# Alimentacion.net
KiCad netlist of a schematic drawn in Altium Designer
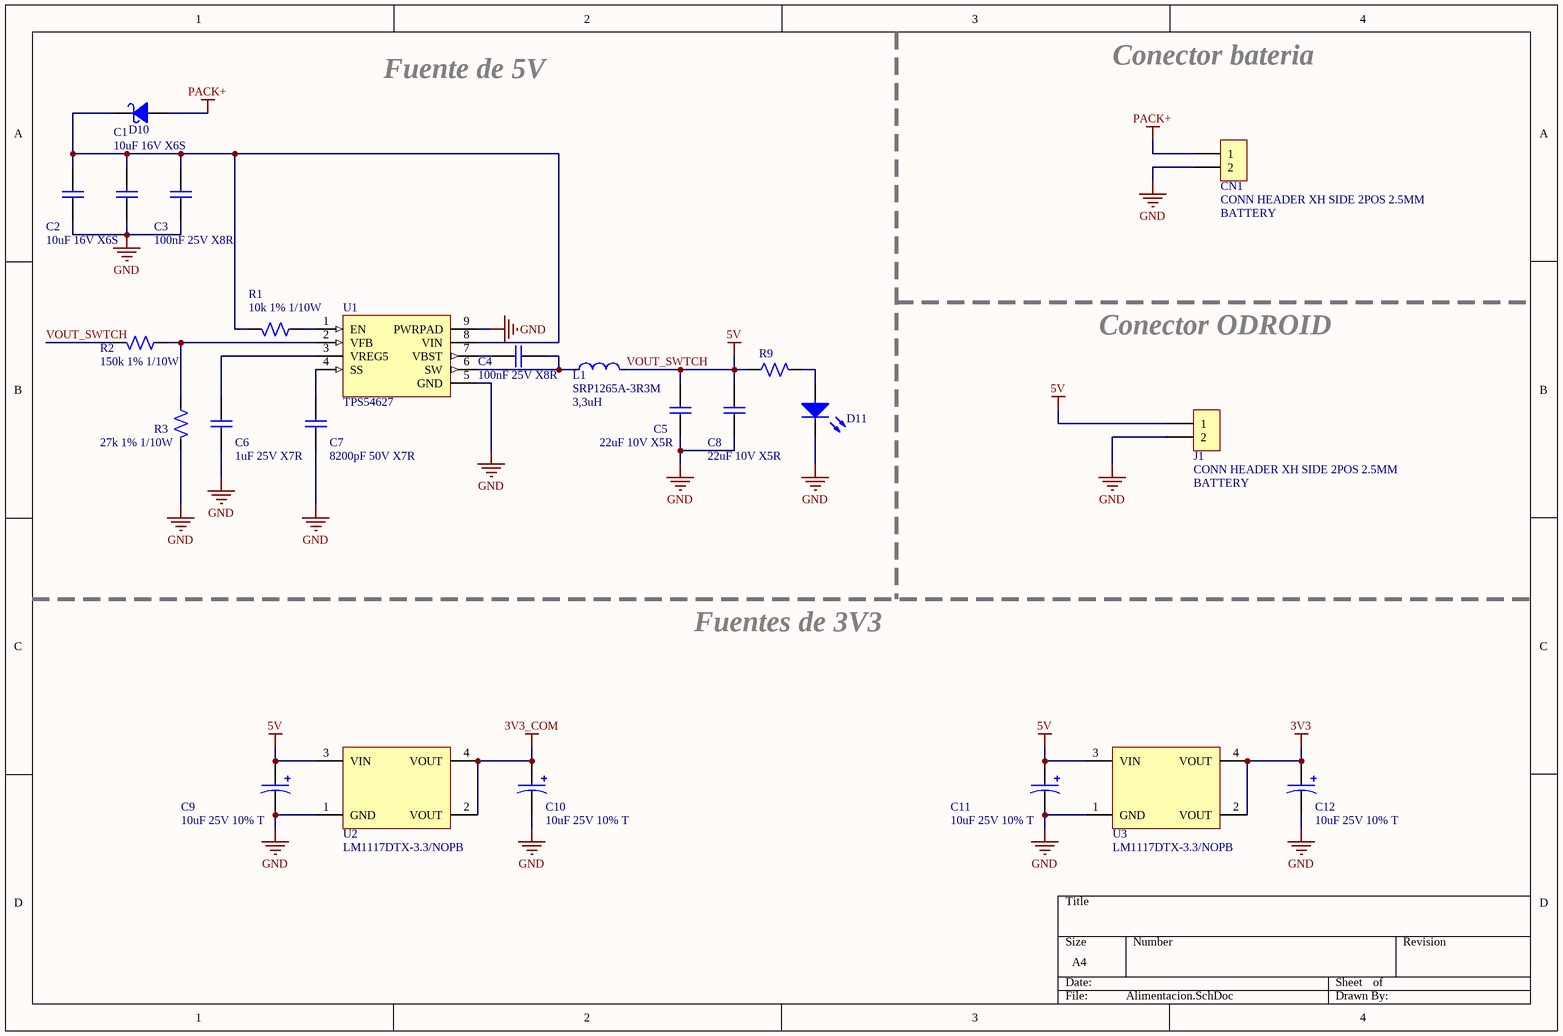
[diagram p0: Alimentacion.SchDoc]

(export (version "E")
  (design (tool "Eeschema 10.0.6"))
  (components
    (comp (ref "C1")
      (value "10uF 16V X6S")
      (footprint "C1206")
      (description "Capacitor de placas paralelas")
      (libsource (lib "HW_Dron_V2") (part "Capacitor"))
    )
    (comp (ref "C2")
      (value "10uF 16V X6S")
      (footprint "C1206")
      (description "Capacitor de placas paralelas")
      (libsource (lib "HW_Dron_V2") (part "Capacitor"))
    )
    (comp (ref "C3")
      (value "100nF 25V X8R")
      (footprint "C1206")
      (description "Capacitor de placas paralelas")
      (libsource (lib "HW_Dron_V2") (part "Capacitor"))
    )
    (comp (ref "C4")
      (value "100nF 25V X8R")
      (footprint "C0603")
      (description "Capacitor de placas paralelas")
      (libsource (lib "HW_Dron_V2") (part "Capacitor"))
    )
    (comp (ref "C5")
      (value "22uF 10V X5R")
      (footprint "C1206")
      (description "Capacitor de placas paralelas")
      (libsource (lib "HW_Dron_V2") (part "Capacitor"))
    )
    (comp (ref "C6")
      (value "1uF 25V X7R")
      (footprint "C0603")
      (description "Capacitor de placas paralelas")
      (libsource (lib "HW_Dron_V2") (part "Capacitor"))
    )
    (comp (ref "C7")
      (value "8200pF 50V X7R")
      (footprint "C0603")
      (description "Capacitor de placas paralelas")
      (libsource (lib "HW_Dron_V2") (part "Capacitor"))
    )
    (comp (ref "C8")
      (value "22uF 10V X5R")
      (footprint "C1206")
      (description "Capacitor de placas paralelas")
      (libsource (lib "HW_Dron_V2") (part "Capacitor"))
    )
    (comp (ref "C9")
      (value "10uF 25V 10% T")
      (footprint "AVX_C")
      (description "Capacitor polarizado")
      (libsource (lib "HW_Dron_V2") (part "CapaPol"))
    )
    (comp (ref "C10")
      (value "10uF 25V 10% T")
      (footprint "AVX_C")
      (description "Capacitor polarizado")
      (libsource (lib "HW_Dron_V2") (part "CapaPol"))
    )
    (comp (ref "C11")
      (value "10uF 25V 10% T")
      (footprint "AVX_C")
      (description "Capacitor polarizado")
      (libsource (lib "HW_Dron_V2") (part "CapaPol"))
    )
    (comp (ref "C12")
      (value "10uF 25V 10% T")
      (footprint "AVX_C")
      (description "Capacitor polarizado")
      (libsource (lib "HW_Dron_V2") (part "CapaPol"))
    )
    (comp (ref "CN1")
      (value "CONN HEADER XH SIDE 2POS 2.5MM")
      (footprint "S2B-XH-A")
      (description "Header, 2-pin")
      (fields (field (name "ALTIUM_UNNAMED_1") "BATTERY"))
      (libsource (lib "HW_Dron_V2") (part "Header_2"))
    )
    (comp (ref "D10")
      (value "Schottky")
      (footprint "SMC (DO-214AB)")
      (description "Diodo Schottky")
      (libsource (lib "HW_Dron_V2") (part "Schottky"))
    )
    (comp (ref "D11")
      (value "Led")
      (footprint "LED_0805")
      (description "Diodo Led")
      (libsource (lib "HW_Dron_V2") (part "Led"))
    )
    (comp (ref "J1")
      (value "CONN HEADER XH SIDE 2POS 2.5MM")
      (footprint "5V_OUT")
      (description "Header, 2-pin")
      (fields (field (name "ALTIUM_UNNAMED_1") "BATTERY"))
      (libsource (lib "HW_Dron_V2") (part "Header_2"))
    )
    (comp (ref "L1")
      (value "SRP1265A-3R3M")
      (footprint "SRP1265A")
      (description "Inductor")
      (fields (field (name "VALOR") "3,3uH"))
      (libsource (lib "HW_Dron_V2") (part "Inductor"))
    )
    (comp (ref "R1")
      (value "10k 1% 1/10W")
      (footprint "R0603")
      (description "Resistencia")
      (libsource (lib "HW_Dron_V2") (part "Resistor"))
    )
    (comp (ref "R2")
      (value "150k 1% 1/10W")
      (footprint "R0603")
      (description "Resistencia")
      (libsource (lib "HW_Dron_V2") (part "Resistor"))
    )
    (comp (ref "R3")
      (value "27k 1% 1/10W")
      (footprint "R0603")
      (description "Resistencia")
      (libsource (lib "HW_Dron_V2") (part "Resistor"))
    )
    (comp (ref "R9")
      (value "~")
      (footprint "R0603")
      (description "Resistencia")
      (libsource (lib "HW_Dron_V2") (part "Resistor"))
    )
    (comp (ref "U1")
      (value "TPS54627")
      (footprint "HSOP-8")
      (description "4.5-V to 18-V Input, 6-A Synchronous Step-Down Converter")
      (libsource (lib "HW_Dron_V2") (part "TPS54627"))
    )
    (comp (ref "U2")
      (value "LM1117DTX-3.3/NOPB")
      (footprint "DPAK")
      (description "Low dropout oscilator")
      (libsource (lib "HW_Dron_V2") (part "LM1117"))
    )
    (comp (ref "U3")
      (value "LM1117DTX-3.3/NOPB")
      (footprint "DPAK")
      (description "Low dropout oscilator")
      (libsource (lib "HW_Dron_V2") (part "LM1117"))
    )
  )
  (nets
    (net (code "1") (name "3V3") (class "Default")
      (node (ref "C12") (pin "1") (pinfunction "1_1") (pintype "passive"))
      (node (ref "U3") (pin "2") (pinfunction "VOUT_2") (pintype "power_in"))
      (node (ref "U3") (pin "4") (pinfunction "VOUT_4") (pintype "power_in"))
    )
    (net (code "2") (name "3V3_COM") (class "Default")
      (node (ref "C10") (pin "1") (pinfunction "1_1") (pintype "passive"))
      (node (ref "U2") (pin "2") (pinfunction "VOUT_2") (pintype "power_in"))
      (node (ref "U2") (pin "4") (pinfunction "VOUT_4") (pintype "power_in"))
    )
    (net (code "3") (name "5V") (class "Default")
      (node (ref "C11") (pin "1") (pinfunction "1_1") (pintype "passive"))
      (node (ref "C5") (pin "1") (pinfunction "1_1") (pintype "passive"))
      (node (ref "C8") (pin "1") (pinfunction "1_1") (pintype "passive"))
      (node (ref "C9") (pin "1") (pinfunction "1_1") (pintype "passive"))
      (node (ref "J1") (pin "1") (pinfunction "1_1") (pintype "passive"))
      (node (ref "L1") (pin "2") (pinfunction "2_2") (pintype "passive"))
      (node (ref "R2") (pin "2") (pinfunction "2_2") (pintype "passive"))
      (node (ref "R9") (pin "1") (pinfunction "1_1") (pintype "passive"))
      (node (ref "U2") (pin "3") (pinfunction "VIN_3") (pintype "power_in"))
      (node (ref "U3") (pin "3") (pinfunction "VIN_3") (pintype "power_in"))
    )
    (net (code "4") (name "GND") (class "Default")
      (node (ref "C1") (pin "2") (pinfunction "2_2") (pintype "passive"))
      (node (ref "C10") (pin "2") (pinfunction "2_2") (pintype "passive"))
      (node (ref "C11") (pin "2") (pinfunction "2_2") (pintype "passive"))
      (node (ref "C12") (pin "2") (pinfunction "2_2") (pintype "passive"))
      (node (ref "C2") (pin "2") (pinfunction "2_2") (pintype "passive"))
      (node (ref "C3") (pin "2") (pinfunction "2_2") (pintype "passive"))
      (node (ref "C5") (pin "2") (pinfunction "2_2") (pintype "passive"))
      (node (ref "C6") (pin "2") (pinfunction "2_2") (pintype "passive"))
      (node (ref "C7") (pin "2") (pinfunction "2_2") (pintype "passive"))
      (node (ref "C8") (pin "2") (pinfunction "2_2") (pintype "passive"))
      (node (ref "C9") (pin "2") (pinfunction "2_2") (pintype "passive"))
      (node (ref "CN1") (pin "2") (pinfunction "2_2") (pintype "passive"))
      (node (ref "D11") (pin "2") (pinfunction "2_2") (pintype "passive"))
      (node (ref "J1") (pin "2") (pinfunction "2_2") (pintype "passive"))
      (node (ref "R3") (pin "2") (pinfunction "2_2") (pintype "passive"))
      (node (ref "U1") (pin "5") (pinfunction "GND_5") (pintype "power_in"))
      (node (ref "U1") (pin "9") (pinfunction "PWRPAD_9") (pintype "power_in"))
      (node (ref "U2") (pin "1") (pinfunction "GND_1") (pintype "power_in"))
      (node (ref "U3") (pin "1") (pinfunction "GND_1") (pintype "power_in"))
    )
    (net (code "5") (name "Net-(D11-Pad1)") (class "Default")
      (node (ref "D11") (pin "1") (pinfunction "1_1") (pintype "passive"))
      (node (ref "R9") (pin "2") (pinfunction "2_2") (pintype "passive"))
    )
    (net (code "6") (name "Net-(U1-EN)") (class "Default")
      (node (ref "R1") (pin "1") (pinfunction "1_1") (pintype "passive"))
      (node (ref "U1") (pin "1") (pinfunction "EN_1") (pintype "input"))
    )
    (net (code "7") (name "Net-(U1-SS)") (class "Default")
      (node (ref "C7") (pin "1") (pinfunction "1_1") (pintype "passive"))
      (node (ref "U1") (pin "4") (pinfunction "SS_4") (pintype "input"))
    )
    (net (code "8") (name "Net-(U1-SW)") (class "Default")
      (node (ref "C4") (pin "2") (pinfunction "2_2") (pintype "passive"))
      (node (ref "L1") (pin "1") (pinfunction "1_1") (pintype "passive"))
      (node (ref "U1") (pin "6") (pinfunction "SW_6") (pintype "output"))
    )
    (net (code "9") (name "Net-(U1-VBST)") (class "Default")
      (node (ref "C4") (pin "1") (pinfunction "1_1") (pintype "passive"))
      (node (ref "U1") (pin "7") (pinfunction "VBST_7") (pintype "output"))
    )
    (net (code "10") (name "Net-(U1-VFB)") (class "Default")
      (node (ref "R2") (pin "1") (pinfunction "1_1") (pintype "passive"))
      (node (ref "R3") (pin "1") (pinfunction "1_1") (pintype "passive"))
      (node (ref "U1") (pin "2") (pinfunction "VFB_2") (pintype "input"))
    )
    (net (code "11") (name "Net-(U1-VIN)") (class "Default")
      (node (ref "C1") (pin "1") (pinfunction "1_1") (pintype "passive"))
      (node (ref "C2") (pin "1") (pinfunction "1_1") (pintype "passive"))
      (node (ref "C3") (pin "1") (pinfunction "1_1") (pintype "passive"))
      (node (ref "D10") (pin "2") (pinfunction "2_2") (pintype "passive"))
      (node (ref "R1") (pin "2") (pinfunction "2_2") (pintype "passive"))
      (node (ref "U1") (pin "8") (pinfunction "VIN_8") (pintype "power_in"))
    )
    (net (code "12") (name "Net-(U1-VREG5)") (class "Default")
      (node (ref "C6") (pin "1") (pinfunction "1_1") (pintype "passive"))
      (node (ref "U1") (pin "3") (pinfunction "VREG5_3") (pintype "passive"))
    )
    (net (code "13") (name "PACK+") (class "Default")
      (node (ref "CN1") (pin "1") (pinfunction "1_1") (pintype "passive"))
      (node (ref "D10") (pin "1") (pinfunction "1_1") (pintype "passive"))
    )
  )
)
